# UCSD_QuadCopter_Rev1.net
KiCad netlist of a schematic drawn in EAGLE
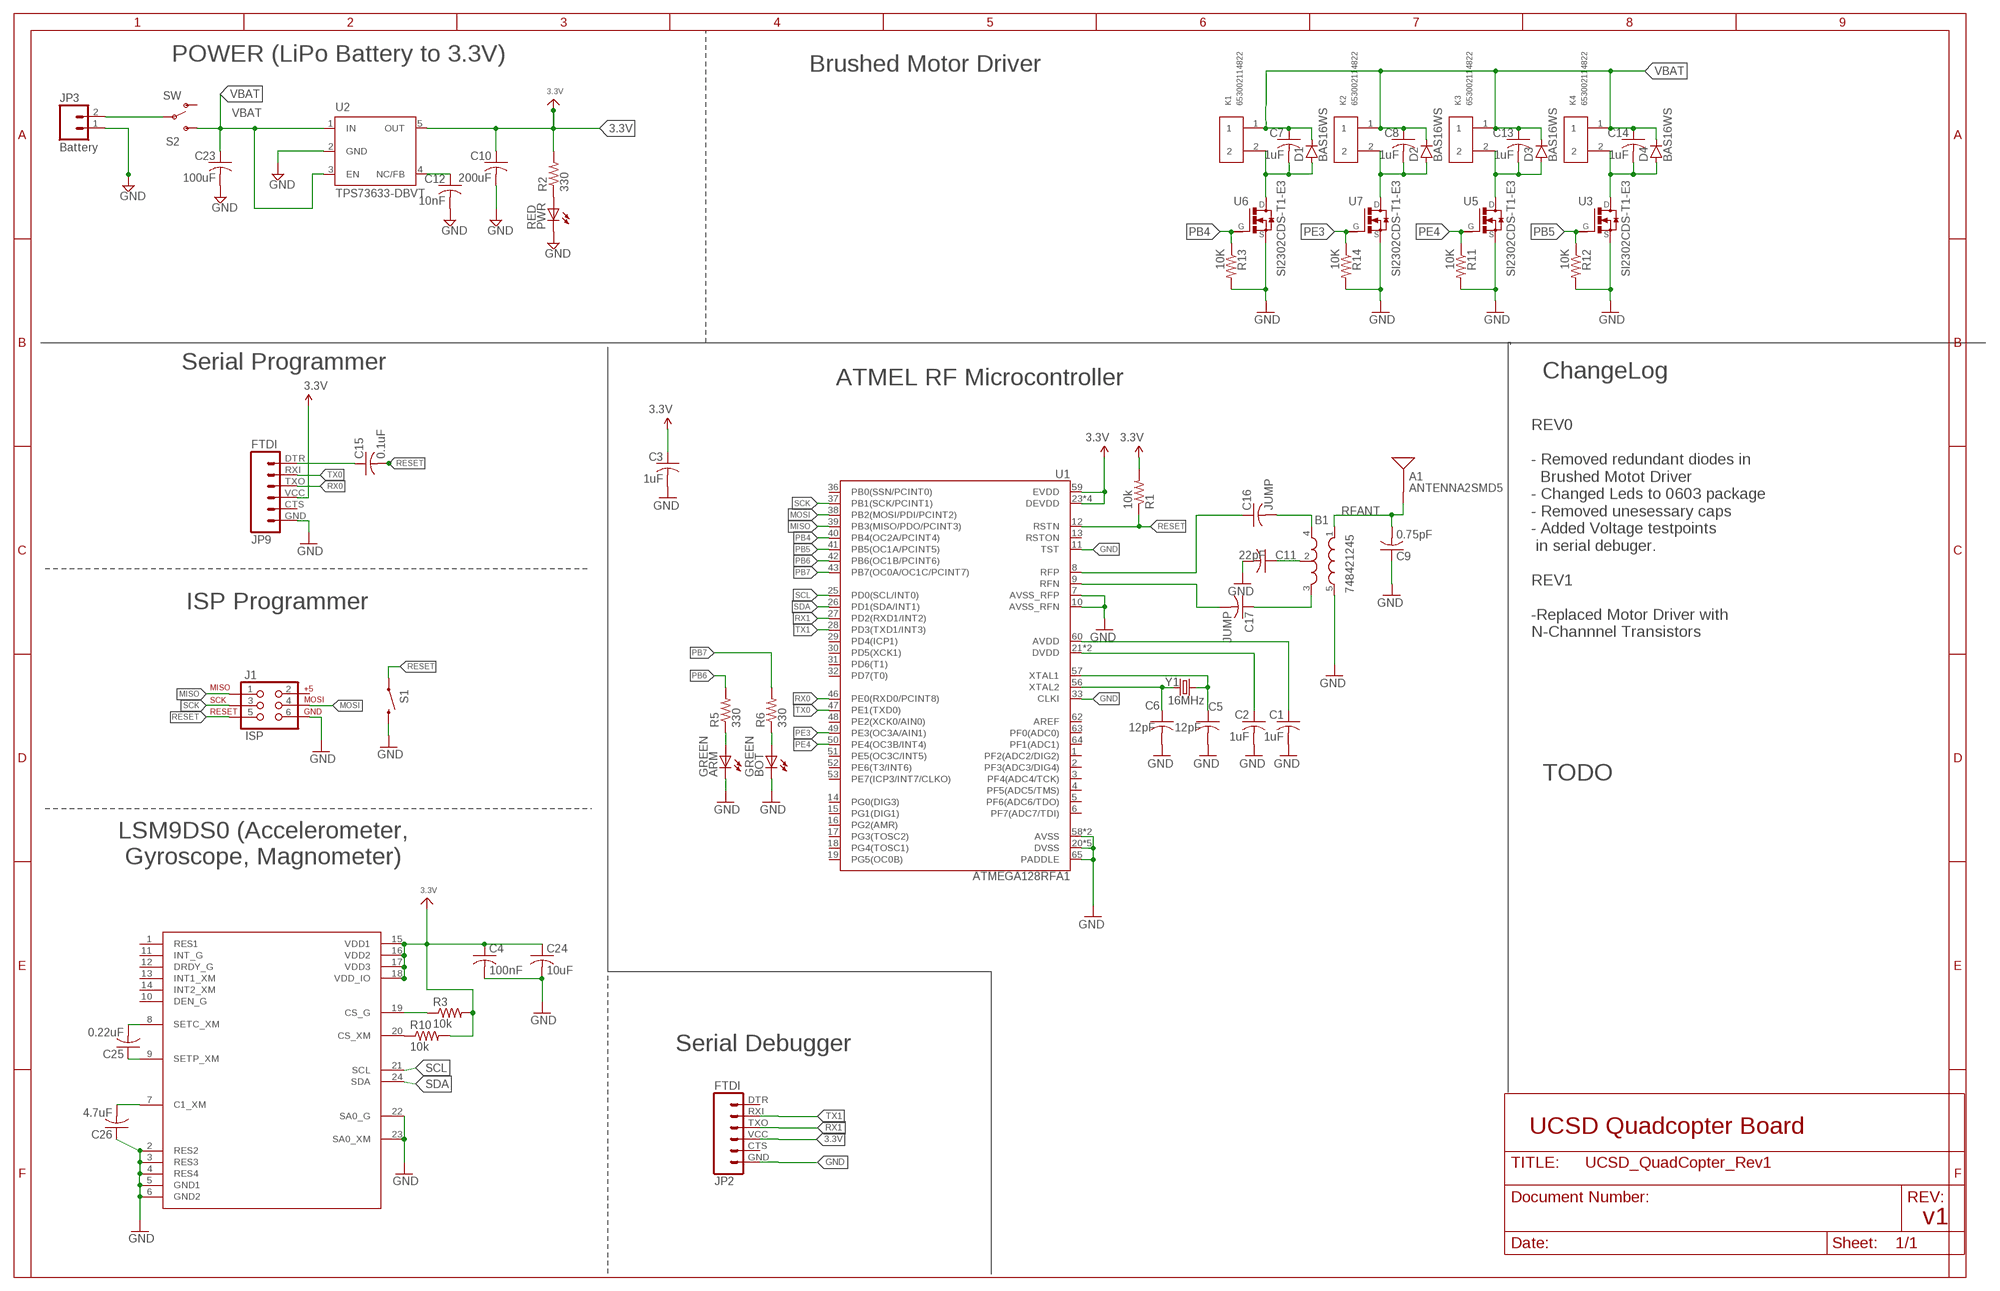
[diagram p0: schematic, sheet 1]

(export (version "E")
  (design (tool "Eeschema 10.0.6"))
  (components
    (comp (ref "A1")
      (value "ANTENNA2SMD5")
      (footprint "eagle-import:ANTENNA-CHIP5")
      (libsource (lib "eagle-import") (part "ANTENNA2SMD5"))
    )
    (comp (ref "ARM")
      (value "GREEN")
      (footprint "eagle-import:CHIP-LED0805")
      (libsource (lib "eagle-import") (part "LEDCHIP-LED0805"))
    )
    (comp (ref "B1")
      (value "748421245")
      (footprint "eagle-import:BALUN")
      (libsource (lib "eagle-import") (part "BALUN0805"))
    )
    (comp (ref "BOT")
      (value "GREEN")
      (footprint "eagle-import:CHIP-LED0805")
      (libsource (lib "eagle-import") (part "LEDCHIP-LED0805"))
    )
    (comp (ref "C1")
      (value "1uF")
      (footprint "eagle-import:C0805")
      (libsource (lib "eagle-import") (part "resistor_C-USC0805"))
    )
    (comp (ref "C2")
      (value "1uF")
      (footprint "eagle-import:C0805")
      (libsource (lib "eagle-import") (part "resistor_C-USC0805"))
    )
    (comp (ref "C3")
      (value "1uF")
      (footprint "eagle-import:C0805")
      (libsource (lib "eagle-import") (part "resistor_C-USC0805"))
    )
    (comp (ref "C4")
      (value "100nF")
      (footprint "eagle-import:C0805")
      (libsource (lib "eagle-import") (part "C-USC0805"))
    )
    (comp (ref "C5")
      (value "12pF")
      (footprint "eagle-import:C0805")
      (libsource (lib "eagle-import") (part "resistor_C-USC0805"))
    )
    (comp (ref "C6")
      (value "12pF")
      (footprint "eagle-import:C0805")
      (libsource (lib "eagle-import") (part "resistor_C-USC0805"))
    )
    (comp (ref "C7")
      (value "1uF")
      (footprint "eagle-import:C0805")
      (libsource (lib "eagle-import") (part "resistor_C-USC0805"))
    )
    (comp (ref "C8")
      (value "1uF")
      (footprint "eagle-import:C0805")
      (libsource (lib "eagle-import") (part "resistor_C-USC0805"))
    )
    (comp (ref "C9")
      (value "0.75pF")
      (footprint "eagle-import:C0805")
      (libsource (lib "eagle-import") (part "resistor_C-USC0805"))
    )
    (comp (ref "C10")
      (value "200uF")
      (footprint "eagle-import:C0805")
      (libsource (lib "eagle-import") (part "resistor_C-USC0805"))
    )
    (comp (ref "C11")
      (value "22pF")
      (footprint "eagle-import:C0805")
      (libsource (lib "eagle-import") (part "resistor_C-USC0805"))
    )
    (comp (ref "C12")
      (value "10nF")
      (footprint "eagle-import:C0805")
      (libsource (lib "eagle-import") (part "resistor_C-USC0805"))
    )
    (comp (ref "C13")
      (value "1uF")
      (footprint "eagle-import:C0805")
      (libsource (lib "eagle-import") (part "resistor_C-USC0805"))
    )
    (comp (ref "C14")
      (value "1uF")
      (footprint "eagle-import:C0805")
      (libsource (lib "eagle-import") (part "resistor_C-USC0805"))
    )
    (comp (ref "C15")
      (value "0.1uF")
      (footprint "eagle-import:C0805")
      (libsource (lib "eagle-import") (part "resistor_C-USC0805"))
    )
    (comp (ref "C16")
      (value "JUMP")
      (footprint "eagle-import:C0805")
      (libsource (lib "eagle-import") (part "resistor_C-USC0805"))
    )
    (comp (ref "C17")
      (value "JUMP")
      (footprint "eagle-import:C0805")
      (libsource (lib "eagle-import") (part "resistor_C-USC0805"))
    )
    (comp (ref "C23")
      (value "100uF")
      (footprint "eagle-import:C0805")
      (libsource (lib "eagle-import") (part "resistor_C-USC0805"))
    )
    (comp (ref "C24")
      (value "10uF")
      (footprint "eagle-import:C0805")
      (libsource (lib "eagle-import") (part "C-USC0805"))
    )
    (comp (ref "C25")
      (value "0.22uF")
      (footprint "eagle-import:C0805")
      (libsource (lib "eagle-import") (part "C-USC0805"))
    )
    (comp (ref "C26")
      (value "4.7uF")
      (footprint "eagle-import:C0805")
      (libsource (lib "eagle-import") (part "C-USC0805"))
    )
    (comp (ref "D1")
      (value "BAS16WS")
      (footprint "eagle-import:SOD323_ST")
      (libsource (lib "eagle-import") (part "BAS16WS"))
    )
    (comp (ref "D2")
      (value "BAS16WS")
      (footprint "eagle-import:SOD323_ST")
      (libsource (lib "eagle-import") (part "BAS16WS"))
    )
    (comp (ref "D3")
      (value "BAS16WS")
      (footprint "eagle-import:SOD323_ST")
      (libsource (lib "eagle-import") (part "BAS16WS"))
    )
    (comp (ref "D4")
      (value "BAS16WS")
      (footprint "eagle-import:SOD323_ST")
      (libsource (lib "eagle-import") (part "BAS16WS"))
    )
    (comp (ref "J1")
      (value "ISP")
      (footprint "eagle-import:2X3-NS")
      (libsource (lib "eagle-import") (part "AVR_SPI_PRG_6NS"))
    )
    (comp (ref "JP2")
      (value "FTDI")
      (footprint "eagle-import:FTDI_BASIC")
      (libsource (lib "eagle-import") (part "FTDI_BASICPTH"))
    )
    (comp (ref "JP3")
      (value "Battery")
      (footprint "eagle-import:1X02")
      (libsource (lib "eagle-import") (part "M02PTH"))
    )
    (comp (ref "JP9")
      (value "FTDI")
      (footprint "eagle-import:FTDI_BASIC")
      (libsource (lib "eagle-import") (part "FTDI_BASICPTH"))
    )
    (comp (ref "K1")
      (value "653002114822")
      (footprint "eagle-import:653002114822")
      (libsource (lib "eagle-import") (part "653002114822"))
    )
    (comp (ref "K2")
      (value "653002114822")
      (footprint "eagle-import:653002114822")
      (libsource (lib "eagle-import") (part "653002114822"))
    )
    (comp (ref "K3")
      (value "653002114822")
      (footprint "eagle-import:653002114822")
      (libsource (lib "eagle-import") (part "653002114822"))
    )
    (comp (ref "K4")
      (value "653002114822")
      (footprint "eagle-import:653002114822")
      (libsource (lib "eagle-import") (part "653002114822"))
    )
    (comp (ref "PWR")
      (value "RED")
      (footprint "eagle-import:CHIP-LED0805")
      (libsource (lib "eagle-import") (part "LEDCHIP-LED0805"))
    )
    (comp (ref "R1")
      (value "10k")
      (footprint "eagle-import:R0805")
      (libsource (lib "eagle-import") (part "R-US_R0805"))
    )
    (comp (ref "R2")
      (value "330")
      (footprint "eagle-import:R0805")
      (libsource (lib "eagle-import") (part "R-US_R0805"))
    )
    (comp (ref "R3")
      (value "10k")
      (footprint "eagle-import:R0805")
      (libsource (lib "eagle-import") (part "R-US_R0805"))
    )
    (comp (ref "R5")
      (value "330")
      (footprint "eagle-import:R0805")
      (libsource (lib "eagle-import") (part "R-US_R0805"))
    )
    (comp (ref "R6")
      (value "330")
      (footprint "eagle-import:R0805")
      (libsource (lib "eagle-import") (part "R-US_R0805"))
    )
    (comp (ref "R10")
      (value "10k")
      (footprint "eagle-import:R0805")
      (libsource (lib "eagle-import") (part "R-US_R0805"))
    )
    (comp (ref "R11")
      (value "10K")
      (footprint "eagle-import:R0805")
      (libsource (lib "eagle-import") (part "R-US_R0805"))
    )
    (comp (ref "R12")
      (value "10K")
      (footprint "eagle-import:R0805")
      (libsource (lib "eagle-import") (part "R-US_R0805"))
    )
    (comp (ref "R13")
      (value "10K")
      (footprint "eagle-import:R0805")
      (libsource (lib "eagle-import") (part "R-US_R0805"))
    )
    (comp (ref "R14")
      (value "10K")
      (footprint "eagle-import:R0805")
      (libsource (lib "eagle-import") (part "R-US_R0805"))
    )
    (comp (ref "S1")
      (value "SWITCH-MOMENTARY-2SMD")
      (footprint "eagle-import:TACTILE_SWITCH_SMD")
      (libsource (lib "eagle-import") (part "SWITCH-MOMENTARY-2SMD"))
    )
    (comp (ref "S2")
      (value "SW")
      (footprint "eagle-import:SWITCH-SPDT")
      (libsource (lib "eagle-import") (part "SWITCH-SPDTPTH"))
    )
    (comp (ref "U1")
      (value "ATMEGA128RFA1")
      (footprint "eagle-import:QFN-64")
      (libsource (lib "eagle-import") (part "ATMEGA128RFA1"))
    )
    (comp (ref "U2")
      (value "TPS73633-DBVT")
      (footprint "eagle-import:SOT23-DBV")
      (libsource (lib "eagle-import") (part "TPS73633-DBVT"))
    )
    (comp (ref "U3")
      (value "SI2302CDS-T1-E3")
      (footprint "eagle-import:SOT95P237X112-3N")
      (libsource (lib "eagle-import") (part "SI2302CDS-T1-E3"))
    )
    (comp (ref "U4")
      (value "LSM9DS0")
      (footprint "eagle-import:LGA-24")
      (libsource (lib "eagle-import") (part "LSM9DS0"))
    )
    (comp (ref "U5")
      (value "SI2302CDS-T1-E3")
      (footprint "eagle-import:SOT95P237X112-3N")
      (libsource (lib "eagle-import") (part "SI2302CDS-T1-E3"))
    )
    (comp (ref "U6")
      (value "SI2302CDS-T1-E3")
      (footprint "eagle-import:SOT95P237X112-3N")
      (libsource (lib "eagle-import") (part "SI2302CDS-T1-E3"))
    )
    (comp (ref "U7")
      (value "SI2302CDS-T1-E3")
      (footprint "eagle-import:SOT95P237X112-3N")
      (libsource (lib "eagle-import") (part "SI2302CDS-T1-E3"))
    )
    (comp (ref "Y1")
      (value "16MHz")
      (footprint "eagle-import:CRYSTAL-SMD-5X3")
      (libsource (lib "eagle-import") (part "CRYSTAL5X3"))
    )
  )
  (nets
    (net (code "1") (name "/RFANT") (class "Default")
      (node (ref "A1") (pin "FEED") (pinfunction "SIGNAL_FEED") (pintype "bidirectional"))
      (node (ref "B1") (pin "1") (pinfunction "IN_1") (pintype "bidirectional"))
      (node (ref "C9") (pin "2") (pinfunction "2_2") (pintype "passive"))
    )
    (net (code "2") (name "3.3V") (class "Default")
      (node (ref "C10") (pin "1") (pinfunction "1_1") (pintype "passive"))
      (node (ref "C24") (pin "1") (pinfunction "1_1") (pintype "passive"))
      (node (ref "C3") (pin "1") (pinfunction "1_1") (pintype "passive"))
      (node (ref "C4") (pin "1") (pinfunction "1_1") (pintype "passive"))
      (node (ref "JP2") (pin "VCC") (pinfunction "4_VCC") (pintype "passive"))
      (node (ref "JP9") (pin "VCC") (pinfunction "4_VCC") (pintype "passive"))
      (node (ref "R1") (pin "2") (pinfunction "2_2") (pintype "passive"))
      (node (ref "R10") (pin "2") (pinfunction "2_2") (pintype "passive"))
      (node (ref "R2") (pin "2") (pinfunction "2_2") (pintype "passive"))
      (node (ref "R3") (pin "2") (pinfunction "2_2") (pintype "passive"))
      (node (ref "U1") (pin "23") (pinfunction "DEVDD_23") (pintype "bidirectional"))
      (node (ref "U1") (pin "34") (pinfunction "DEVDD_34") (pintype "bidirectional"))
      (node (ref "U1") (pin "44") (pinfunction "DEVDD_44") (pintype "bidirectional"))
      (node (ref "U1") (pin "54") (pinfunction "DEVDD_54") (pintype "bidirectional"))
      (node (ref "U1") (pin "59") (pinfunction "EVDD_59") (pintype "bidirectional"))
      (node (ref "U2") (pin "5") (pinfunction "OUT_5") (pintype "passive"))
      (node (ref "U4") (pin "15") (pinfunction "VDD1_15") (pintype "bidirectional"))
      (node (ref "U4") (pin "16") (pinfunction "VDD2_16") (pintype "bidirectional"))
      (node (ref "U4") (pin "17") (pinfunction "VDD3_17") (pintype "bidirectional"))
      (node (ref "U4") (pin "18") (pinfunction "VDD_IO_18") (pintype "bidirectional"))
    )
    (net (code "3") (name "GND") (class "Default")
      (node (ref "ARM") (pin "C") (pinfunction "C_C") (pintype "passive"))
      (node (ref "B1") (pin "5") (pinfunction "GND_5") (pintype "bidirectional"))
      (node (ref "BOT") (pin "C") (pinfunction "C_C") (pintype "passive"))
      (node (ref "C1") (pin "2") (pinfunction "2_2") (pintype "passive"))
      (node (ref "C10") (pin "2") (pinfunction "2_2") (pintype "passive"))
      (node (ref "C11") (pin "2") (pinfunction "2_2") (pintype "passive"))
      (node (ref "C12") (pin "2") (pinfunction "2_2") (pintype "passive"))
      (node (ref "C2") (pin "2") (pinfunction "2_2") (pintype "passive"))
      (node (ref "C23") (pin "2") (pinfunction "2_2") (pintype "passive"))
      (node (ref "C24") (pin "2") (pinfunction "2_2") (pintype "passive"))
      (node (ref "C26") (pin "1") (pinfunction "1_1") (pintype "passive"))
      (node (ref "C3") (pin "2") (pinfunction "2_2") (pintype "passive"))
      (node (ref "C4") (pin "2") (pinfunction "2_2") (pintype "passive"))
      (node (ref "C5") (pin "2") (pinfunction "2_2") (pintype "passive"))
      (node (ref "C6") (pin "2") (pinfunction "2_2") (pintype "passive"))
      (node (ref "C9") (pin "1") (pinfunction "1_1") (pintype "passive"))
      (node (ref "J1") (pin "6") (pinfunction "6_6") (pintype "passive"))
      (node (ref "JP2") (pin "GND") (pinfunction "6_GND") (pintype "passive"))
      (node (ref "JP3") (pin "1") (pinfunction "1_1") (pintype "passive"))
      (node (ref "JP9") (pin "GND") (pinfunction "6_GND") (pintype "passive"))
      (node (ref "PWR") (pin "C") (pinfunction "C_C") (pintype "passive"))
      (node (ref "R11") (pin "2") (pinfunction "2_2") (pintype "passive"))
      (node (ref "R12") (pin "2") (pinfunction "2_2") (pintype "passive"))
      (node (ref "R13") (pin "2") (pinfunction "2_2") (pintype "passive"))
      (node (ref "R14") (pin "2") (pinfunction "2_2") (pintype "passive"))
      (node (ref "S1") (pin "3") (pinfunction "2_3") (pintype "passive"))
      (node (ref "U1") (pin "10") (pinfunction "AVSS_RFN_10") (pintype "bidirectional"))
      (node (ref "U1") (pin "11") (pinfunction "TST_11") (pintype "bidirectional"))
      (node (ref "U1") (pin "20") (pinfunction "DVSS_20") (pintype "bidirectional"))
      (node (ref "U1") (pin "24") (pinfunction "DVSS_24") (pintype "bidirectional"))
      (node (ref "U1") (pin "33") (pinfunction "CLKI_33") (pintype "bidirectional"))
      (node (ref "U1") (pin "35") (pinfunction "DVSS_35") (pintype "bidirectional"))
      (node (ref "U1") (pin "45") (pinfunction "DVSS_45") (pintype "bidirectional"))
      (node (ref "U1") (pin "55") (pinfunction "DVSS_55") (pintype "bidirectional"))
      (node (ref "U1") (pin "58") (pinfunction "AVSS_58") (pintype "bidirectional"))
      (node (ref "U1") (pin "61") (pinfunction "AVSS_61") (pintype "bidirectional"))
      (node (ref "U1") (pin "65") (pinfunction "PADDLE_65") (pintype "bidirectional"))
      (node (ref "U1") (pin "7") (pinfunction "AVSS_RFP_7") (pintype "bidirectional"))
      (node (ref "U2") (pin "2") (pinfunction "GND_2") (pintype "input"))
      (node (ref "U3") (pin "2") (pinfunction "S_2") (pintype "passive"))
      (node (ref "U4") (pin "2") (pinfunction "RES2_2") (pintype "bidirectional"))
      (node (ref "U4") (pin "22") (pinfunction "SA0_G_22") (pintype "bidirectional"))
      (node (ref "U4") (pin "23") (pinfunction "SA0_XM_23") (pintype "bidirectional"))
      (node (ref "U4") (pin "3") (pinfunction "RES3_3") (pintype "bidirectional"))
      (node (ref "U4") (pin "4") (pinfunction "RES4_4") (pintype "bidirectional"))
      (node (ref "U4") (pin "5") (pinfunction "GND1_5") (pintype "bidirectional"))
      (node (ref "U4") (pin "6") (pinfunction "GND2_6") (pintype "bidirectional"))
      (node (ref "U5") (pin "2") (pinfunction "S_2") (pintype "passive"))
      (node (ref "U6") (pin "2") (pinfunction "S_2") (pintype "passive"))
      (node (ref "U7") (pin "2") (pinfunction "S_2") (pintype "passive"))
    )
    (net (code "4") (name "MISO") (class "Default")
      (node (ref "J1") (pin "1") (pinfunction "1_1") (pintype "passive"))
      (node (ref "U1") (pin "39") (pinfunction "PB3(MISO/PDO/PCINT3)_39") (pintype "bidirectional"))
    )
    (net (code "5") (name "MOSI") (class "Default")
      (node (ref "J1") (pin "4") (pinfunction "4_4") (pintype "passive"))
      (node (ref "U1") (pin "38") (pinfunction "PB2(MOSI/PDI/PCINT2)_38") (pintype "bidirectional"))
    )
    (net (code "6") (name "Net-(ARM-PadA)") (class "Default")
      (node (ref "ARM") (pin "A") (pinfunction "A_A") (pintype "passive"))
      (node (ref "R5") (pin "1") (pinfunction "1_1") (pintype "passive"))
    )
    (net (code "7") (name "Net-(B1-GND-Pad2)") (class "Default")
      (node (ref "B1") (pin "2") (pinfunction "GND_2") (pintype "bidirectional"))
      (node (ref "C11") (pin "1") (pinfunction "1_1") (pintype "passive"))
    )
    (net (code "8") (name "Net-(B1-OUT1)") (class "Default")
      (node (ref "B1") (pin "4") (pinfunction "OUT1_4") (pintype "bidirectional"))
      (node (ref "C16") (pin "2") (pinfunction "2_2") (pintype "passive"))
    )
    (net (code "9") (name "Net-(B1-OUT2)") (class "Default")
      (node (ref "B1") (pin "3") (pinfunction "OUT2_3") (pintype "bidirectional"))
      (node (ref "C17") (pin "1") (pinfunction "1_1") (pintype "passive"))
    )
    (net (code "10") (name "Net-(BOT-PadA)") (class "Default")
      (node (ref "BOT") (pin "A") (pinfunction "A_A") (pintype "passive"))
      (node (ref "R6") (pin "1") (pinfunction "1_1") (pintype "passive"))
    )
    (net (code "11") (name "Net-(C2-Pad1)") (class "Default")
      (node (ref "C2") (pin "1") (pinfunction "1_1") (pintype "passive"))
      (node (ref "U1") (pin "21") (pinfunction "DVDD_21") (pintype "bidirectional"))
      (node (ref "U1") (pin "22") (pinfunction "DVDD_22") (pintype "bidirectional"))
    )
    (net (code "12") (name "Net-(JP9-1)") (class "Default")
      (node (ref "C15") (pin "1") (pinfunction "1_1") (pintype "passive"))
      (node (ref "JP9") (pin "DTR") (pinfunction "1_DTR") (pintype "passive"))
    )
    (net (code "13") (name "Net-(PWR-PadA)") (class "Default")
      (node (ref "PWR") (pin "A") (pinfunction "A_A") (pintype "passive"))
      (node (ref "R2") (pin "1") (pinfunction "1_1") (pintype "passive"))
    )
    (net (code "14") (name "Net-(S2-P)") (class "Default")
      (node (ref "JP3") (pin "2") (pinfunction "2_2") (pintype "passive"))
      (node (ref "S2") (pin "2") (pinfunction "P_2") (pintype "passive"))
    )
    (net (code "15") (name "Net-(U1-AVDD)") (class "Default")
      (node (ref "C1") (pin "1") (pinfunction "1_1") (pintype "passive"))
      (node (ref "U1") (pin "60") (pinfunction "AVDD_60") (pintype "bidirectional"))
    )
    (net (code "16") (name "Net-(U1-RFN)") (class "Default")
      (node (ref "C17") (pin "2") (pinfunction "2_2") (pintype "passive"))
      (node (ref "U1") (pin "9") (pinfunction "RFN_9") (pintype "bidirectional"))
    )
    (net (code "17") (name "Net-(U1-RFP)") (class "Default")
      (node (ref "C16") (pin "1") (pinfunction "1_1") (pintype "passive"))
      (node (ref "U1") (pin "8") (pinfunction "RFP_8") (pintype "bidirectional"))
    )
    (net (code "18") (name "Net-(U1-XTAL1)") (class "Default")
      (node (ref "C5") (pin "1") (pinfunction "1_1") (pintype "passive"))
      (node (ref "U1") (pin "57") (pinfunction "XTAL1_57") (pintype "bidirectional"))
      (node (ref "Y1") (pin "3") (pinfunction "2_3") (pintype "passive"))
    )
    (net (code "19") (name "Net-(U1-XTAL2)") (class "Default")
      (node (ref "C6") (pin "1") (pinfunction "1_1") (pintype "passive"))
      (node (ref "U1") (pin "56") (pinfunction "XTAL2_56") (pintype "bidirectional"))
      (node (ref "Y1") (pin "1") (pinfunction "1_1") (pintype "passive"))
    )
    (net (code "20") (name "Net-(U2-NC{slash}FB)") (class "Default")
      (node (ref "C12") (pin "1") (pinfunction "1_1") (pintype "passive"))
      (node (ref "U2") (pin "4") (pinfunction "NC/FB_4") (pintype "passive"))
    )
    (net (code "21") (name "Net-(U3-D)") (class "Default")
      (node (ref "C14") (pin "2") (pinfunction "2_2") (pintype "passive"))
      (node (ref "D4") (pin "A") (pinfunction "A_A") (pintype "passive"))
      (node (ref "K4") (pin "2") (pinfunction "2_2") (pintype "bidirectional"))
      (node (ref "U3") (pin "3") (pinfunction "D_3") (pintype "passive"))
    )
    (net (code "22") (name "Net-(U4-C1_XM)") (class "Default")
      (node (ref "C26") (pin "2") (pinfunction "2_2") (pintype "passive"))
      (node (ref "U4") (pin "7") (pinfunction "C1_XM_7") (pintype "bidirectional"))
    )
    (net (code "23") (name "Net-(U4-CS_G)") (class "Default")
      (node (ref "R3") (pin "1") (pinfunction "1_1") (pintype "passive"))
      (node (ref "U4") (pin "19") (pinfunction "CS_G_19") (pintype "bidirectional"))
    )
    (net (code "24") (name "Net-(U4-CS_XM)") (class "Default")
      (node (ref "R10") (pin "1") (pinfunction "1_1") (pintype "passive"))
      (node (ref "U4") (pin "20") (pinfunction "CS_XM_20") (pintype "bidirectional"))
    )
    (net (code "25") (name "Net-(U4-SETC_XM)") (class "Default")
      (node (ref "C25") (pin "2") (pinfunction "2_2") (pintype "passive"))
      (node (ref "U4") (pin "8") (pinfunction "SETC_XM_8") (pintype "bidirectional"))
    )
    (net (code "26") (name "Net-(U4-SETP_XM)") (class "Default")
      (node (ref "C25") (pin "1") (pinfunction "1_1") (pintype "passive"))
      (node (ref "U4") (pin "9") (pinfunction "SETP_XM_9") (pintype "bidirectional"))
    )
    (net (code "27") (name "Net-(U5-D)") (class "Default")
      (node (ref "C13") (pin "2") (pinfunction "2_2") (pintype "passive"))
      (node (ref "D3") (pin "A") (pinfunction "A_A") (pintype "passive"))
      (node (ref "K3") (pin "2") (pinfunction "2_2") (pintype "bidirectional"))
      (node (ref "U5") (pin "3") (pinfunction "D_3") (pintype "passive"))
    )
    (net (code "28") (name "Net-(U6-D)") (class "Default")
      (node (ref "C7") (pin "2") (pinfunction "2_2") (pintype "passive"))
      (node (ref "D1") (pin "A") (pinfunction "A_A") (pintype "passive"))
      (node (ref "K1") (pin "2") (pinfunction "2_2") (pintype "bidirectional"))
      (node (ref "U6") (pin "3") (pinfunction "D_3") (pintype "passive"))
    )
    (net (code "29") (name "Net-(U7-D)") (class "Default")
      (node (ref "C8") (pin "2") (pinfunction "2_2") (pintype "passive"))
      (node (ref "D2") (pin "A") (pinfunction "A_A") (pintype "passive"))
      (node (ref "K2") (pin "2") (pinfunction "2_2") (pintype "bidirectional"))
      (node (ref "U7") (pin "3") (pinfunction "D_3") (pintype "passive"))
    )
    (net (code "30") (name "PB4") (class "Default")
      (node (ref "R13") (pin "1") (pinfunction "1_1") (pintype "passive"))
      (node (ref "U1") (pin "40") (pinfunction "PB4(OC2A/PCINT4)_40") (pintype "bidirectional"))
      (node (ref "U6") (pin "1") (pinfunction "G_1") (pintype "passive"))
    )
    (net (code "31") (name "PB5") (class "Default")
      (node (ref "R12") (pin "1") (pinfunction "1_1") (pintype "passive"))
      (node (ref "U1") (pin "41") (pinfunction "PB5(OC1A/PCINT5)_41") (pintype "bidirectional"))
      (node (ref "U3") (pin "1") (pinfunction "G_1") (pintype "passive"))
    )
    (net (code "32") (name "PB6") (class "Default")
      (node (ref "R5") (pin "2") (pinfunction "2_2") (pintype "passive"))
      (node (ref "U1") (pin "42") (pinfunction "PB6(OC1B/PCINT6)_42") (pintype "bidirectional"))
    )
    (net (code "33") (name "PB7") (class "Default")
      (node (ref "R6") (pin "2") (pinfunction "2_2") (pintype "passive"))
      (node (ref "U1") (pin "43") (pinfunction "PB7(OC0A/OC1C/PCINT7)_43") (pintype "bidirectional"))
    )
    (net (code "34") (name "PE3") (class "Default")
      (node (ref "R14") (pin "1") (pinfunction "1_1") (pintype "passive"))
      (node (ref "U1") (pin "49") (pinfunction "PE3(OC3A/AIN1)_49") (pintype "bidirectional"))
      (node (ref "U7") (pin "1") (pinfunction "G_1") (pintype "passive"))
    )
    (net (code "35") (name "PE4") (class "Default")
      (node (ref "R11") (pin "1") (pinfunction "1_1") (pintype "passive"))
      (node (ref "U1") (pin "50") (pinfunction "PE4(OC3B/INT4)_50") (pintype "bidirectional"))
      (node (ref "U5") (pin "1") (pinfunction "G_1") (pintype "passive"))
    )
    (net (code "36") (name "RESET") (class "Default")
      (node (ref "C15") (pin "2") (pinfunction "2_2") (pintype "passive"))
      (node (ref "J1") (pin "5") (pinfunction "5_5") (pintype "passive"))
      (node (ref "R1") (pin "1") (pinfunction "1_1") (pintype "passive"))
      (node (ref "S1") (pin "1") (pinfunction "1_1") (pintype "passive"))
      (node (ref "U1") (pin "12") (pinfunction "RSTN_12") (pintype "bidirectional"))
    )
    (net (code "37") (name "RX0") (class "Default")
      (node (ref "JP9") (pin "TXO") (pinfunction "3_TXO") (pintype "passive"))
      (node (ref "U1") (pin "46") (pinfunction "PE0(RXD0/PCINT8)_46") (pintype "bidirectional"))
    )
    (net (code "38") (name "RX1") (class "Default")
      (node (ref "JP2") (pin "TXO") (pinfunction "3_TXO") (pintype "passive"))
      (node (ref "U1") (pin "27") (pinfunction "PD2(RXD1/INT2)_27") (pintype "bidirectional"))
    )
    (net (code "39") (name "SCK") (class "Default")
      (node (ref "J1") (pin "3") (pinfunction "3_3") (pintype "passive"))
      (node (ref "U1") (pin "37") (pinfunction "PB1(SCK/PCINT1)_37") (pintype "bidirectional"))
    )
    (net (code "40") (name "SCL") (class "Default")
      (node (ref "U1") (pin "25") (pinfunction "PD0(SCL/INT0)_25") (pintype "bidirectional"))
      (node (ref "U4") (pin "21") (pinfunction "SCL_21") (pintype "bidirectional"))
    )
    (net (code "41") (name "SDA") (class "Default")
      (node (ref "U1") (pin "26") (pinfunction "PD1(SDA/INT1)_26") (pintype "bidirectional"))
      (node (ref "U4") (pin "24") (pinfunction "SDA_24") (pintype "bidirectional"))
    )
    (net (code "42") (name "TX0") (class "Default")
      (node (ref "JP9") (pin "RXI") (pinfunction "2_RXI") (pintype "passive"))
      (node (ref "U1") (pin "47") (pinfunction "PE1(TXD0)_47") (pintype "bidirectional"))
    )
    (net (code "43") (name "TX1") (class "Default")
      (node (ref "JP2") (pin "RXI") (pinfunction "2_RXI") (pintype "passive"))
      (node (ref "U1") (pin "28") (pinfunction "PD3(TXD1/INT3)_28") (pintype "bidirectional"))
    )
    (net (code "44") (name "VBAT") (class "Default")
      (node (ref "C13") (pin "1") (pinfunction "1_1") (pintype "passive"))
      (node (ref "C14") (pin "1") (pinfunction "1_1") (pintype "passive"))
      (node (ref "C23") (pin "1") (pinfunction "1_1") (pintype "passive"))
      (node (ref "C7") (pin "1") (pinfunction "1_1") (pintype "passive"))
      (node (ref "C8") (pin "1") (pinfunction "1_1") (pintype "passive"))
      (node (ref "D1") (pin "C") (pinfunction "C_C") (pintype "passive"))
      (node (ref "D2") (pin "C") (pinfunction "C_C") (pintype "passive"))
      (node (ref "D3") (pin "C") (pinfunction "C_C") (pintype "passive"))
      (node (ref "D4") (pin "C") (pinfunction "C_C") (pintype "passive"))
      (node (ref "K1") (pin "1") (pinfunction "1_1") (pintype "bidirectional"))
      (node (ref "K2") (pin "1") (pinfunction "1_1") (pintype "bidirectional"))
      (node (ref "K3") (pin "1") (pinfunction "1_1") (pintype "bidirectional"))
      (node (ref "K4") (pin "1") (pinfunction "1_1") (pintype "bidirectional"))
      (node (ref "S2") (pin "3") (pinfunction "S_3") (pintype "passive"))
      (node (ref "U2") (pin "1") (pinfunction "IN_1") (pintype "input"))
      (node (ref "U2") (pin "3") (pinfunction "EN_3") (pintype "power_in"))
    )
    (net (code "45") (name "unconnected-(J1-Pad2)") (class "Default")
      (node (ref "J1") (pin "2") (pinfunction "2_2") (pintype "passive"))
    )
    (net (code "46") (name "unconnected-(JP2-1-PadDTR)") (class "Default")
      (node (ref "JP2") (pin "DTR") (pinfunction "1_DTR") (pintype "passive"))
    )
    (net (code "47") (name "unconnected-(JP2-5-PadCTS)") (class "Default")
      (node (ref "JP2") (pin "CTS") (pinfunction "5_CTS") (pintype "passive"))
    )
    (net (code "48") (name "unconnected-(JP9-5-PadCTS)") (class "Default")
      (node (ref "JP9") (pin "CTS") (pinfunction "5_CTS") (pintype "passive"))
    )
    (net (code "49") (name "unconnected-(S2-O-Pad1)") (class "Default")
      (node (ref "S2") (pin "1") (pinfunction "O_1") (pintype "passive"))
    )
    (net (code "50") (name "unconnected-(U1-AREF-Pad62)") (class "Default")
      (node (ref "U1") (pin "62") (pinfunction "AREF_62") (pintype "bidirectional"))
    )
    (net (code "51") (name "unconnected-(U1-PB0(SSN{slash}PCINT0)-Pad36)") (class "Default")
      (node (ref "U1") (pin "36") (pinfunction "PB0(SSN/PCINT0)_36") (pintype "bidirectional"))
    )
    (net (code "52") (name "unconnected-(U1-PD4(ICP1)-Pad29)") (class "Default")
      (node (ref "U1") (pin "29") (pinfunction "PD4(ICP1)_29") (pintype "bidirectional"))
    )
    (net (code "53") (name "unconnected-(U1-PD5(XCK1)-Pad30)") (class "Default")
      (node (ref "U1") (pin "30") (pinfunction "PD5(XCK1)_30") (pintype "bidirectional"))
    )
    (net (code "54") (name "unconnected-(U1-PD6(T1)-Pad31)") (class "Default")
      (node (ref "U1") (pin "31") (pinfunction "PD6(T1)_31") (pintype "bidirectional"))
    )
    (net (code "55") (name "unconnected-(U1-PD7(T0)-Pad32)") (class "Default")
      (node (ref "U1") (pin "32") (pinfunction "PD7(T0)_32") (pintype "bidirectional"))
    )
    (net (code "56") (name "unconnected-(U1-PE2(XCK0{slash}AIN0)-Pad48)") (class "Default")
      (node (ref "U1") (pin "48") (pinfunction "PE2(XCK0/AIN0)_48") (pintype "bidirectional"))
    )
    (net (code "57") (name "unconnected-(U1-PE5(OC3C{slash}INT5)-Pad51)") (class "Default")
      (node (ref "U1") (pin "51") (pinfunction "PE5(OC3C/INT5)_51") (pintype "bidirectional"))
    )
    (net (code "58") (name "unconnected-(U1-PE6(T3{slash}INT6)-Pad52)") (class "Default")
      (node (ref "U1") (pin "52") (pinfunction "PE6(T3/INT6)_52") (pintype "bidirectional"))
    )
    (net (code "59") (name "unconnected-(U1-PE7(ICP3{slash}INT7{slash}CLKO)-Pad53)") (class "Default")
      (node (ref "U1") (pin "53") (pinfunction "PE7(ICP3/INT7/CLKO)_53") (pintype "bidirectional"))
    )
    (net (code "60") (name "unconnected-(U1-PF0(ADC0)-Pad63)") (class "Default")
      (node (ref "U1") (pin "63") (pinfunction "PF0(ADC0)_63") (pintype "bidirectional"))
    )
    (net (code "61") (name "unconnected-(U1-PF1(ADC1)-Pad64)") (class "Default")
      (node (ref "U1") (pin "64") (pinfunction "PF1(ADC1)_64") (pintype "bidirectional"))
    )
    (net (code "62") (name "unconnected-(U1-PF2(ADC2{slash}DIG2)-Pad1)") (class "Default")
      (node (ref "U1") (pin "1") (pinfunction "PF2(ADC2/DIG2)_1") (pintype "bidirectional"))
    )
    (net (code "63") (name "unconnected-(U1-PF3(ADC3{slash}DIG4)-Pad2)") (class "Default")
      (node (ref "U1") (pin "2") (pinfunction "PF3(ADC3/DIG4)_2") (pintype "bidirectional"))
    )
    (net (code "64") (name "unconnected-(U1-PF4(ADC4{slash}TCK)-Pad3)") (class "Default")
      (node (ref "U1") (pin "3") (pinfunction "PF4(ADC4/TCK)_3") (pintype "bidirectional"))
    )
    (net (code "65") (name "unconnected-(U1-PF5(ADC5{slash}TMS)-Pad4)") (class "Default")
      (node (ref "U1") (pin "4") (pinfunction "PF5(ADC5/TMS)_4") (pintype "bidirectional"))
    )
    (net (code "66") (name "unconnected-(U1-PF6(ADC6{slash}TDO)-Pad5)") (class "Default")
      (node (ref "U1") (pin "5") (pinfunction "PF6(ADC6/TDO)_5") (pintype "bidirectional"))
    )
    (net (code "67") (name "unconnected-(U1-PF7(ADC7{slash}TDI)-Pad6)") (class "Default")
      (node (ref "U1") (pin "6") (pinfunction "PF7(ADC7/TDI)_6") (pintype "bidirectional"))
    )
    (net (code "68") (name "unconnected-(U1-PG0(DIG3)-Pad14)") (class "Default")
      (node (ref "U1") (pin "14") (pinfunction "PG0(DIG3)_14") (pintype "bidirectional"))
    )
    (net (code "69") (name "unconnected-(U1-PG1(DIG1)-Pad15)") (class "Default")
      (node (ref "U1") (pin "15") (pinfunction "PG1(DIG1)_15") (pintype "bidirectional"))
    )
    (net (code "70") (name "unconnected-(U1-PG2(AMR)-Pad16)") (class "Default")
      (node (ref "U1") (pin "16") (pinfunction "PG2(AMR)_16") (pintype "bidirectional"))
    )
    (net (code "71") (name "unconnected-(U1-PG3(TOSC2)-Pad17)") (class "Default")
      (node (ref "U1") (pin "17") (pinfunction "PG3(TOSC2)_17") (pintype "bidirectional"))
    )
    (net (code "72") (name "unconnected-(U1-PG4(TOSC1)-Pad18)") (class "Default")
      (node (ref "U1") (pin "18") (pinfunction "PG4(TOSC1)_18") (pintype "bidirectional"))
    )
    (net (code "73") (name "unconnected-(U1-PG5(OC0B)-Pad19)") (class "Default")
      (node (ref "U1") (pin "19") (pinfunction "PG5(OC0B)_19") (pintype "bidirectional"))
    )
    (net (code "74") (name "unconnected-(U1-RSTON-Pad13)") (class "Default")
      (node (ref "U1") (pin "13") (pinfunction "RSTON_13") (pintype "bidirectional"))
    )
    (net (code "75") (name "unconnected-(U4-DEN_G-Pad10)") (class "Default")
      (node (ref "U4") (pin "10") (pinfunction "DEN_G_10") (pintype "bidirectional"))
    )
    (net (code "76") (name "unconnected-(U4-DRDY_G-Pad12)") (class "Default")
      (node (ref "U4") (pin "12") (pinfunction "DRDY_G_12") (pintype "bidirectional"))
    )
    (net (code "77") (name "unconnected-(U4-INT1_XM-Pad13)") (class "Default")
      (node (ref "U4") (pin "13") (pinfunction "INT1_XM_13") (pintype "bidirectional"))
    )
    (net (code "78") (name "unconnected-(U4-INT2_XM-Pad14)") (class "Default")
      (node (ref "U4") (pin "14") (pinfunction "INT2_XM_14") (pintype "bidirectional"))
    )
    (net (code "79") (name "unconnected-(U4-INT_G-Pad11)") (class "Default")
      (node (ref "U4") (pin "11") (pinfunction "INT_G_11") (pintype "bidirectional"))
    )
    (net (code "80") (name "unconnected-(U4-RES1-Pad1)") (class "Default")
      (node (ref "U4") (pin "1") (pinfunction "RES1_1") (pintype "bidirectional"))
    )
  )
)
